# 1-Schematic_power_supply.net
KiCad netlist of a schematic drawn in EasyEDA
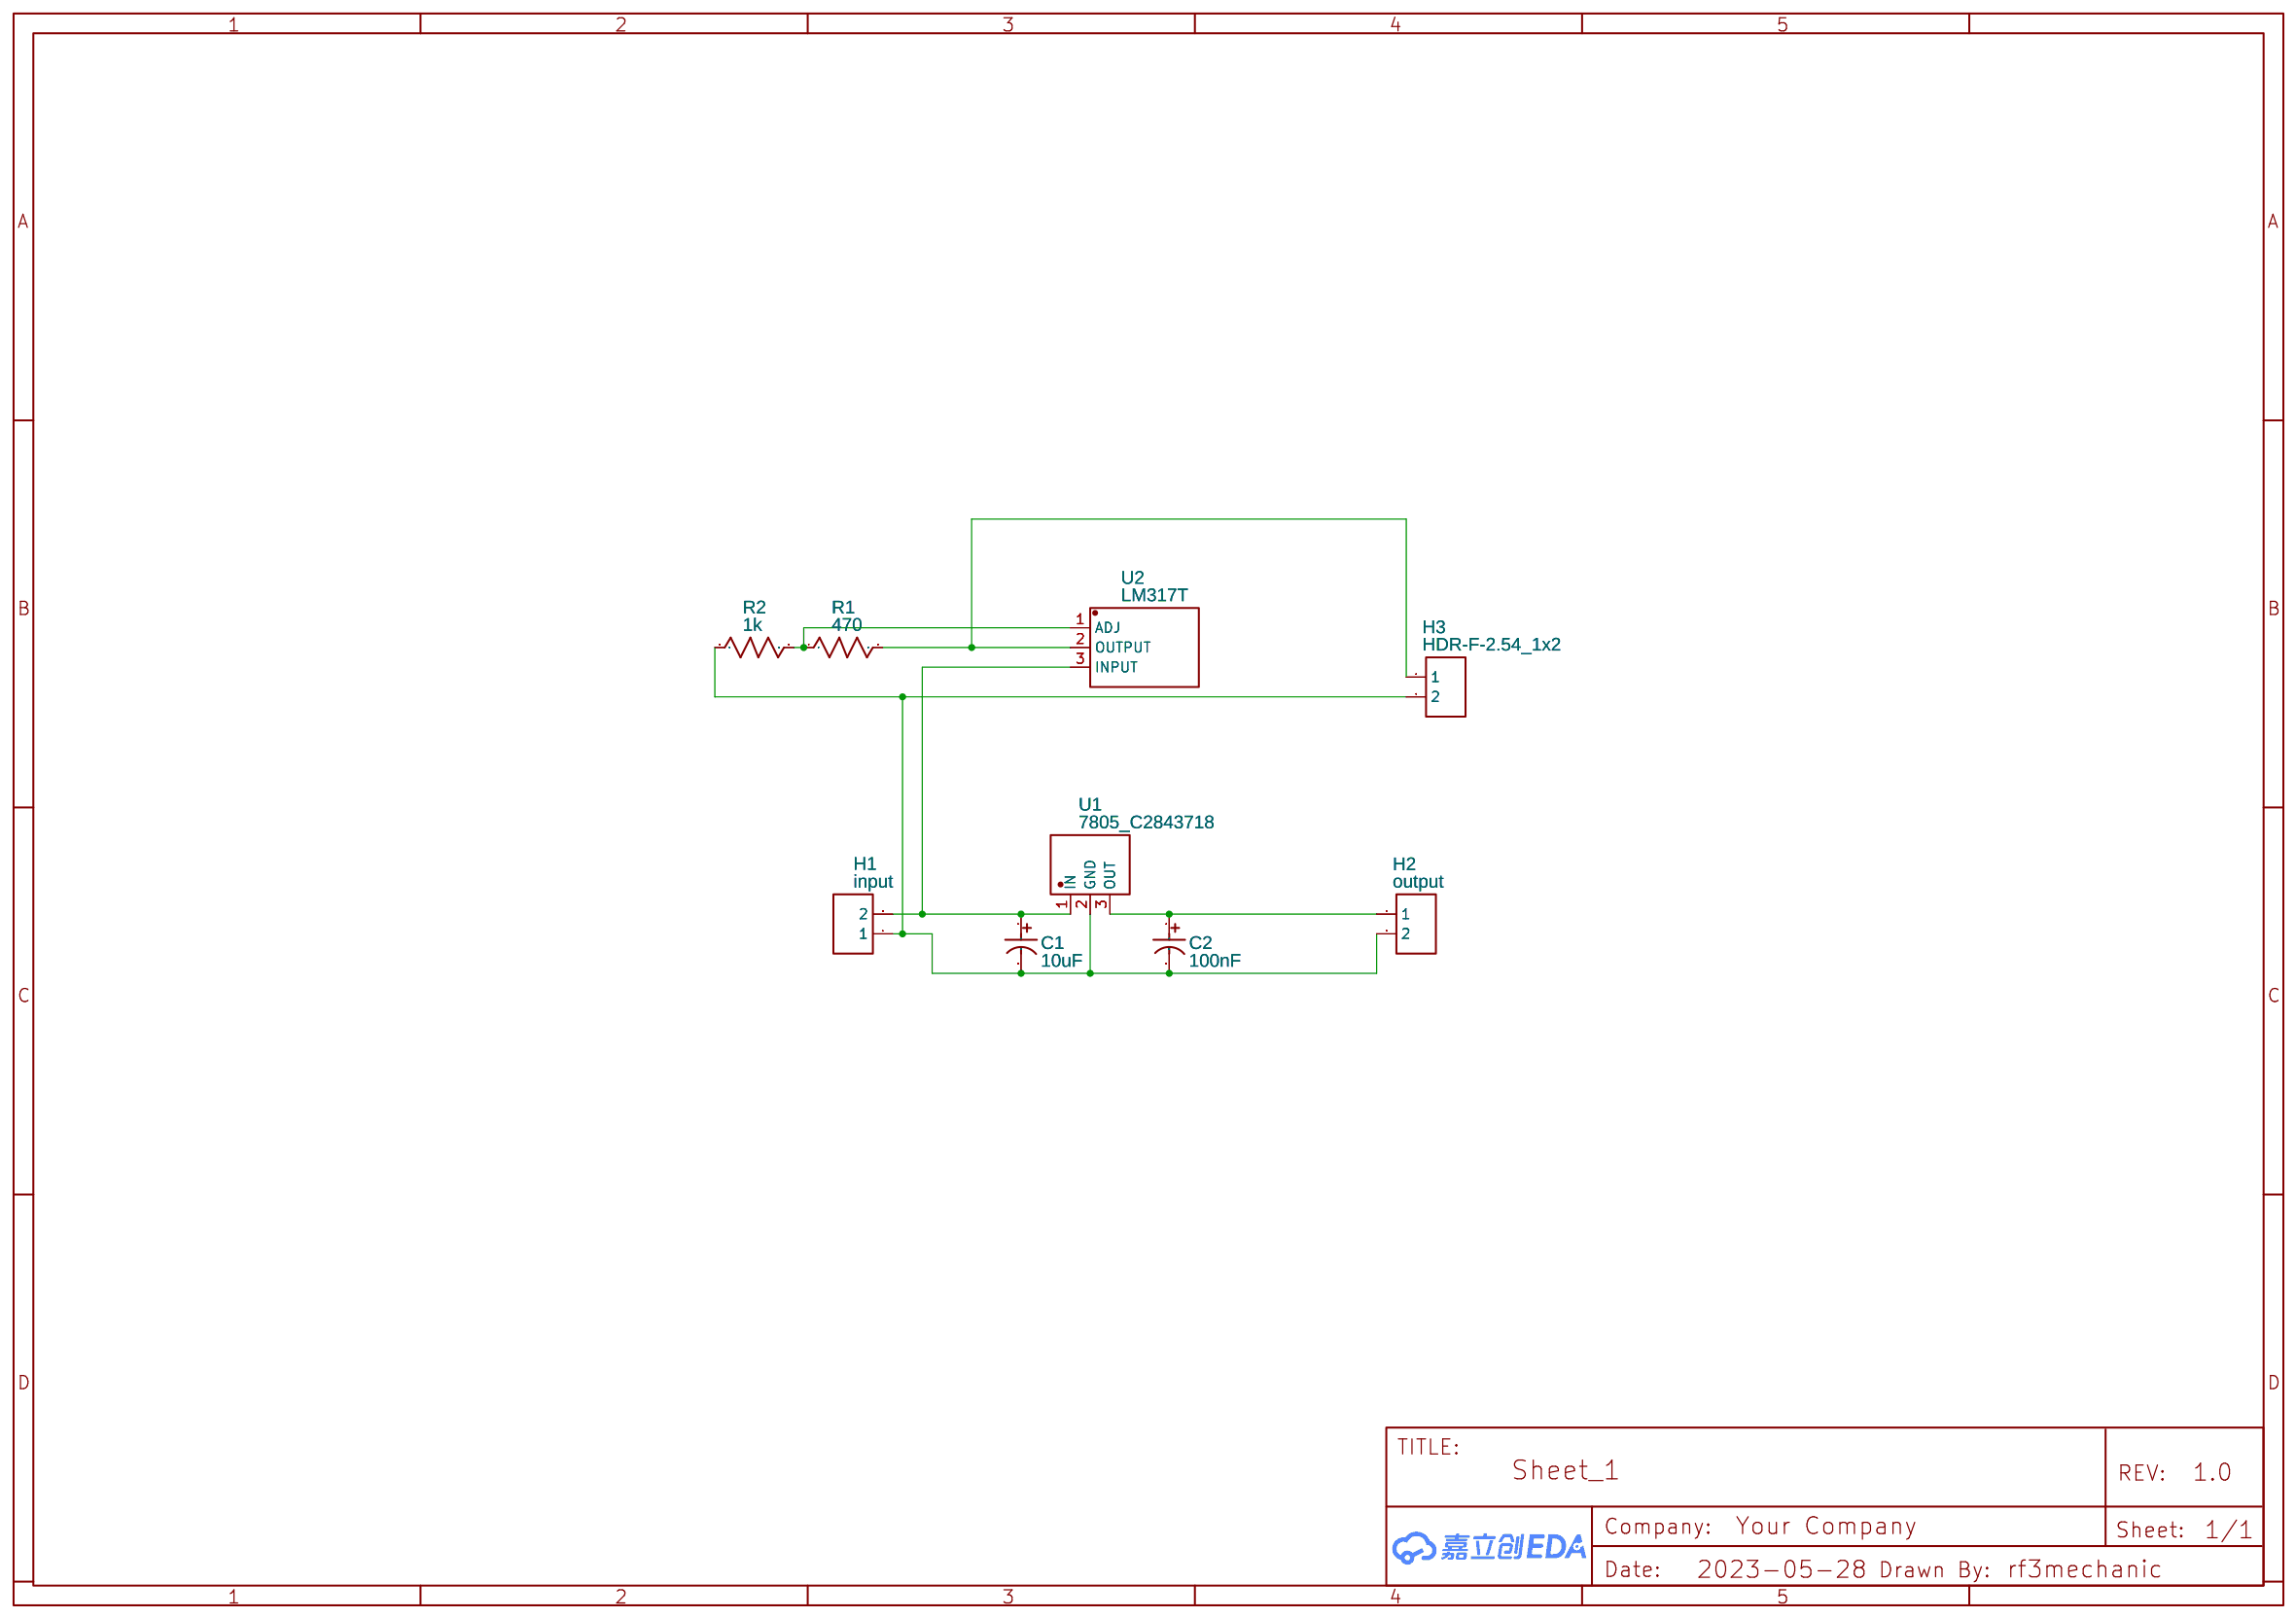
[diagram p0: schematic sheet]

(export (version "E")
  (design (tool "Eeschema 10.0.6"))
  (components
    (comp (ref "C1")
      (value "10uF")
      (fields
        (field (name "BOM_Manufacturer Part") "KM106M016D11RR0VH2FP0")
        (field (name "BOM_Supplier Part") "C43799")
      )
      (libsource (lib "") (part "10uF 16V 5*11"))
    )
    (comp (ref "C2")
      (value "100nF")
      (fields
        (field (name "BOM_Manufacturer Part") "KM104M050D11RR0VH2FP0")
        (field (name "BOM_Supplier Part") "C28061")
      )
      (libsource (lib "") (part "0.1UF 50V"))
    )
    (comp (ref "H1")
      (value "input")
      (fields (field (name "BOM_Supplier Part") "C49661"))
      (libsource (lib "") (part "HDR-F-2.54_1x2_1"))
    )
    (comp (ref "H2")
      (value "output")
      (fields (field (name "BOM_Supplier Part") "C49661"))
      (libsource (lib "") (part "HDR-F-2.54_1x2"))
    )
    (comp (ref "H3")
      (value "HDR-F-2.54_1x2")
      (fields (field (name "BOM_Supplier Part") "C49661"))
      (libsource (lib "") (part "HDR-F-2.54_1x2"))
    )
    (comp (ref "R1") (value "470") (libsource (lib "") (part "R_AXIAL-0.4_US")))
    (comp (ref "R2") (value "1k") (libsource (lib "") (part "R_AXIAL-0.4_US")))
    (comp (ref "U1")
      (value "7805_C2843718")
      (fields (field (name "BOM_Manufacturer Part") "7805") (field (name "BOM_Supplier Part") "C2843718"))
      (libsource (lib "") (part "7805_C2843718"))
    )
    (comp (ref "U2")
      (value "LM317T")
      (fields (field (name "BOM_Supplier Part") "C361026"))
      (libsource (lib "") (part "LM317T"))
    )
  )
  (nets
    (net (code "1") (name "Net-(U1-GND)") (class "Default")
      (node (ref "C1") (pin "2") (pinfunction "2_2") (pintype "input"))
      (node (ref "C2") (pin "2") (pinfunction "2_2") (pintype "input"))
      (node (ref "H1") (pin "1") (pinfunction "1_1") (pintype "input"))
      (node (ref "H2") (pin "2") (pinfunction "2_2") (pintype "input"))
      (node (ref "H3") (pin "2") (pinfunction "2_2") (pintype "input"))
      (node (ref "R2") (pin "1") (pinfunction "1_1") (pintype "unspecified"))
      (node (ref "U1") (pin "2") (pinfunction "GND_2") (pintype "unspecified"))
    )
    (net (code "2") (name "Net-(U1-IN)") (class "Default")
      (node (ref "C1") (pin "1") (pinfunction "1_1") (pintype "input"))
      (node (ref "H1") (pin "2") (pinfunction "2_2") (pintype "input"))
      (node (ref "U1") (pin "1") (pinfunction "IN_1") (pintype "unspecified"))
      (node (ref "U2") (pin "3") (pinfunction "INPUT_3") (pintype "unspecified"))
    )
    (net (code "3") (name "Net-(U1-OUT)") (class "Default")
      (node (ref "C2") (pin "1") (pinfunction "1_1") (pintype "input"))
      (node (ref "H2") (pin "1") (pinfunction "1_1") (pintype "input"))
      (node (ref "U1") (pin "3") (pinfunction "OUT_3") (pintype "unspecified"))
    )
    (net (code "4") (name "Net-(U2-ADJ)") (class "Default")
      (node (ref "R1") (pin "1") (pinfunction "1_1") (pintype "unspecified"))
      (node (ref "R2") (pin "2") (pinfunction "2_2") (pintype "unspecified"))
      (node (ref "U2") (pin "1") (pinfunction "ADJ_1") (pintype "unspecified"))
    )
    (net (code "5") (name "Net-(U2-OUTPUT)") (class "Default")
      (node (ref "H3") (pin "1") (pinfunction "1_1") (pintype "input"))
      (node (ref "R1") (pin "2") (pinfunction "2_2") (pintype "unspecified"))
      (node (ref "U2") (pin "2") (pinfunction "OUTPUT_2") (pintype "unspecified"))
    )
  )
)
